# final.net
KiCad netlist of a schematic drawn in EAGLE
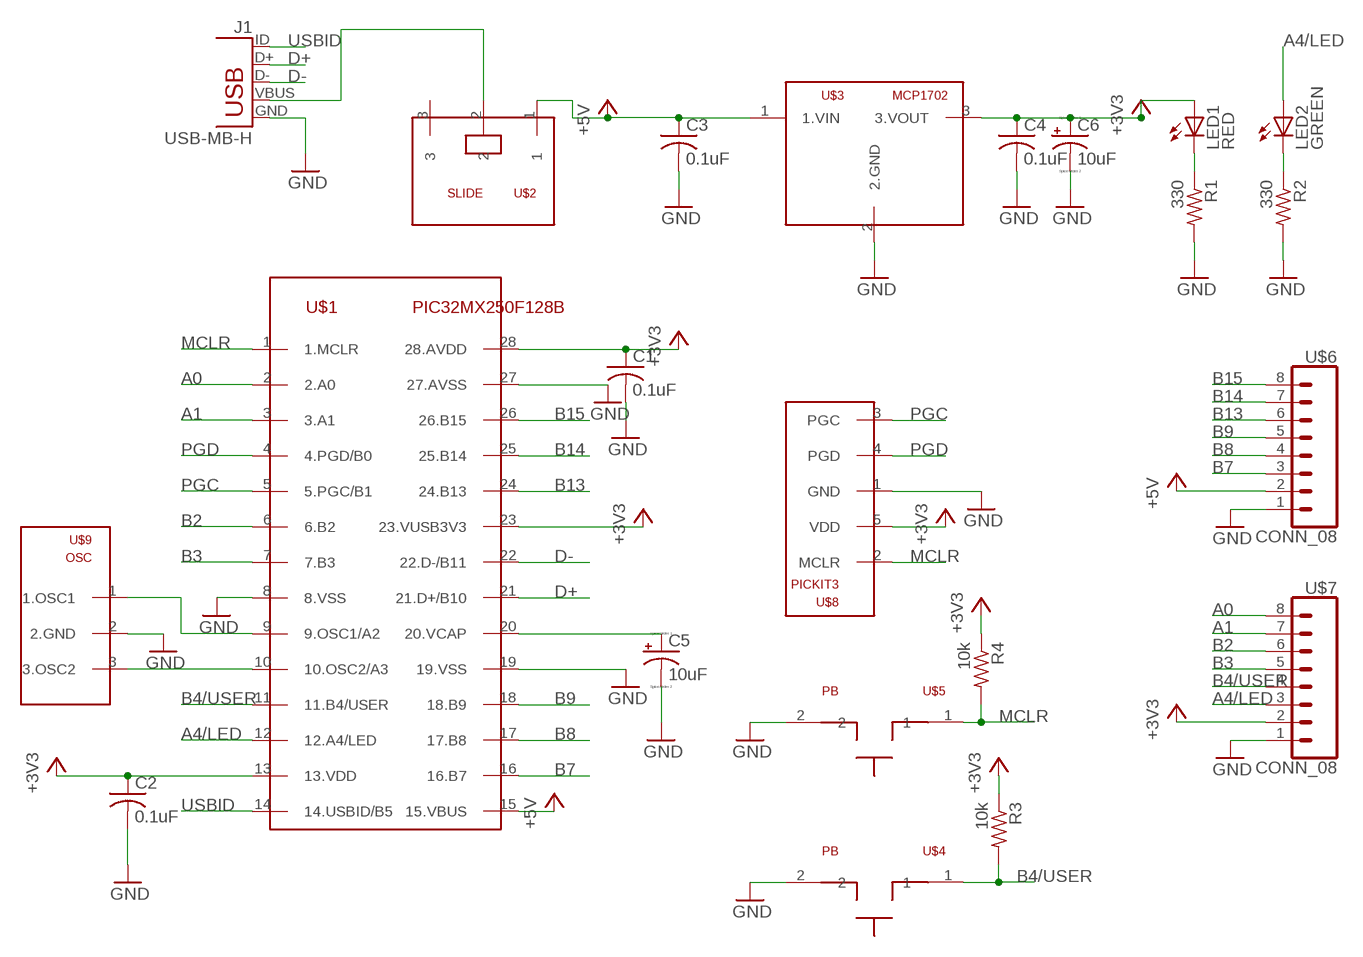
[diagram p0: schematic, sheet 1]

(export (version "E")
  (design (tool "Eeschema 10.0.6"))
  (components
    (comp (ref "C1")
      (value "0.1uF")
      (footprint "eagle-import:C025-025X050")
      (libsource (lib "eagle-import") (part "C-US025-025X050"))
    )
    (comp (ref "C2")
      (value "0.1uF")
      (footprint "eagle-import:C025-025X050")
      (libsource (lib "eagle-import") (part "C-US025-025X050"))
    )
    (comp (ref "C3")
      (value "0.1uF")
      (footprint "eagle-import:C025-025X050")
      (libsource (lib "eagle-import") (part "C-US025-025X050"))
    )
    (comp (ref "C4")
      (value "0.1uF")
      (footprint "eagle-import:C025-025X050")
      (libsource (lib "eagle-import") (part "C-US025-025X050"))
    )
    (comp (ref "C5")
      (value "10uF")
      (footprint "eagle-import:B45181B")
      (libsource (lib "eagle-import") (part "CPOL-USB45181B"))
    )
    (comp (ref "C6")
      (value "10uF")
      (footprint "eagle-import:B45181B")
      (libsource (lib "eagle-import") (part "CPOL-USB45181B"))
    )
    (comp (ref "J1")
      (value "USB-MB-H")
      (footprint "eagle-import:USB-MB-H")
      (libsource (lib "eagle-import") (part "USB-MB-H"))
    )
    (comp (ref "LED1")
      (value "RED")
      (footprint "eagle-import:LED3MM")
      (libsource (lib "eagle-import") (part "LED3MM"))
    )
    (comp (ref "LED2")
      (value "GREEN")
      (footprint "eagle-import:LED3MM")
      (libsource (lib "eagle-import") (part "LED3MM"))
    )
    (comp (ref "R1")
      (value "330")
      (footprint "eagle-import:0207_7")
      (libsource (lib "eagle-import") (part "R-US_0207/7"))
    )
    (comp (ref "R2")
      (value "330")
      (footprint "eagle-import:0207_7")
      (libsource (lib "eagle-import") (part "R-US_0207/7"))
    )
    (comp (ref "R3")
      (value "10k")
      (footprint "eagle-import:0207_7")
      (libsource (lib "eagle-import") (part "R-US_0207/7"))
    )
    (comp (ref "R4")
      (value "10k")
      (footprint "eagle-import:0207_7")
      (libsource (lib "eagle-import") (part "R-US_0207/7"))
    )
    (comp (ref "U$1")
      (value "PIC32MX250F128B")
      (footprint "eagle-import:DIL28-3")
      (libsource (lib "eagle-import") (part "PIC32MX250F128B"))
    )
    (comp (ref "U$2")
      (value "SLIDE")
      (footprint "eagle-import:SLIDE")
      (libsource (lib "eagle-import") (part "SLIDE"))
    )
    (comp (ref "U$3")
      (value "MCP1702")
      (footprint "eagle-import:TO92")
      (libsource (lib "eagle-import") (part "MCP1702"))
    )
    (comp (ref "U$4") (value "PB") (footprint "eagle-import:PB") (libsource (lib "eagle-import") (part "PB")))
    (comp (ref "U$5") (value "PB") (footprint "eagle-import:PB") (libsource (lib "eagle-import") (part "PB")))
    (comp (ref "U$6")
      (value "CONN_08")
      (footprint "eagle-import:1X08")
      (libsource (lib "eagle-import") (part "CONN_08"))
    )
    (comp (ref "U$7")
      (value "CONN_08")
      (footprint "eagle-import:1X08")
      (libsource (lib "eagle-import") (part "CONN_08"))
    )
    (comp (ref "U$8")
      (value "PICKIT3")
      (footprint "eagle-import:1X05")
      (libsource (lib "eagle-import") (part "PICKIT3"))
    )
    (comp (ref "U$9")
      (value "OSC")
      (footprint "eagle-import:OSC")
      (libsource (lib "eagle-import") (part "OSC"))
    )
  )
  (nets
    (net (code "1") (name "+3V3") (class "Default")
      (node (ref "C1") (pin "1") (pinfunction "1_1") (pintype "passive"))
      (node (ref "C2") (pin "1") (pinfunction "1_1") (pintype "passive"))
      (node (ref "C4") (pin "1") (pinfunction "1_1") (pintype "passive"))
      (node (ref "C6") (pin "+") (pinfunction "+_+") (pintype "passive"))
      (node (ref "LED1") (pin "A") (pinfunction "A_A") (pintype "passive"))
      (node (ref "R3") (pin "1") (pinfunction "1_1") (pintype "passive"))
      (node (ref "R4") (pin "1") (pinfunction "1_1") (pintype "passive"))
      (node (ref "U$1") (pin "13") (pinfunction "13.VDD_13") (pintype "bidirectional"))
      (node (ref "U$1") (pin "23") (pinfunction "23.VUSB3V3_23") (pintype "bidirectional"))
      (node (ref "U$1") (pin "28") (pinfunction "28.AVDD_28") (pintype "bidirectional"))
      (node (ref "U$3") (pin "3") (pinfunction "3.VOUT_3") (pintype "bidirectional"))
      (node (ref "U$7") (pin "2") (pinfunction "2_2") (pintype "passive"))
      (node (ref "U$8") (pin "5") (pinfunction "VDD_5") (pintype "bidirectional"))
    )
    (net (code "2") (name "+5V") (class "Default")
      (node (ref "C3") (pin "1") (pinfunction "1_1") (pintype "passive"))
      (node (ref "U$1") (pin "15") (pinfunction "15.VBUS_15") (pintype "bidirectional"))
      (node (ref "U$2") (pin "1") (pinfunction "1_1") (pintype "bidirectional"))
      (node (ref "U$3") (pin "1") (pinfunction "1.VIN_1") (pintype "bidirectional"))
      (node (ref "U$6") (pin "2") (pinfunction "2_2") (pintype "passive"))
    )
    (net (code "3") (name "/A0") (class "Default")
      (node (ref "U$1") (pin "2") (pinfunction "2.A0_2") (pintype "bidirectional"))
      (node (ref "U$7") (pin "8") (pinfunction "8_8") (pintype "passive"))
    )
    (net (code "4") (name "/A1") (class "Default")
      (node (ref "U$1") (pin "3") (pinfunction "3.A1_3") (pintype "bidirectional"))
      (node (ref "U$7") (pin "7") (pinfunction "7_7") (pintype "passive"))
    )
    (net (code "5") (name "/A4{slash}LED") (class "Default")
      (node (ref "LED2") (pin "A") (pinfunction "A_A") (pintype "passive"))
      (node (ref "U$1") (pin "12") (pinfunction "12.A4/LED_12") (pintype "bidirectional"))
      (node (ref "U$7") (pin "3") (pinfunction "3_3") (pintype "passive"))
    )
    (net (code "6") (name "/B2") (class "Default")
      (node (ref "U$1") (pin "6") (pinfunction "6.B2_6") (pintype "bidirectional"))
      (node (ref "U$7") (pin "6") (pinfunction "6_6") (pintype "passive"))
    )
    (net (code "7") (name "/B3") (class "Default")
      (node (ref "U$1") (pin "7") (pinfunction "7.B3_7") (pintype "bidirectional"))
      (node (ref "U$7") (pin "5") (pinfunction "5_5") (pintype "passive"))
    )
    (net (code "8") (name "/B4{slash}USER") (class "Default")
      (node (ref "R3") (pin "2") (pinfunction "2_2") (pintype "passive"))
      (node (ref "U$1") (pin "11") (pinfunction "11.B4/USER_11") (pintype "bidirectional"))
      (node (ref "U$4") (pin "1") (pinfunction "1_1") (pintype "bidirectional"))
      (node (ref "U$7") (pin "4") (pinfunction "4_4") (pintype "passive"))
    )
    (net (code "9") (name "/B7") (class "Default")
      (node (ref "U$1") (pin "16") (pinfunction "16.B7_16") (pintype "bidirectional"))
      (node (ref "U$6") (pin "3") (pinfunction "3_3") (pintype "passive"))
    )
    (net (code "10") (name "/B8") (class "Default")
      (node (ref "U$1") (pin "17") (pinfunction "17.B8_17") (pintype "bidirectional"))
      (node (ref "U$6") (pin "4") (pinfunction "4_4") (pintype "passive"))
    )
    (net (code "11") (name "/B9") (class "Default")
      (node (ref "U$1") (pin "18") (pinfunction "18.B9_18") (pintype "bidirectional"))
      (node (ref "U$6") (pin "5") (pinfunction "5_5") (pintype "passive"))
    )
    (net (code "12") (name "/B13") (class "Default")
      (node (ref "U$1") (pin "24") (pinfunction "24.B13_24") (pintype "bidirectional"))
      (node (ref "U$6") (pin "6") (pinfunction "6_6") (pintype "passive"))
    )
    (net (code "13") (name "/B14") (class "Default")
      (node (ref "U$1") (pin "25") (pinfunction "25.B14_25") (pintype "bidirectional"))
      (node (ref "U$6") (pin "7") (pinfunction "7_7") (pintype "passive"))
    )
    (net (code "14") (name "/B15") (class "Default")
      (node (ref "U$1") (pin "26") (pinfunction "26.B15_26") (pintype "bidirectional"))
      (node (ref "U$6") (pin "8") (pinfunction "8_8") (pintype "passive"))
    )
    (net (code "15") (name "/D+") (class "Default")
      (node (ref "J1") (pin "D+") (pinfunction "D+_D+") (pintype "bidirectional"))
      (node (ref "U$1") (pin "21") (pinfunction "21.D+/B10_21") (pintype "bidirectional"))
    )
    (net (code "16") (name "/D-") (class "Default")
      (node (ref "J1") (pin "D-") (pinfunction "D-_D-") (pintype "bidirectional"))
      (node (ref "U$1") (pin "22") (pinfunction "22.D-/B11_22") (pintype "bidirectional"))
    )
    (net (code "17") (name "/MCLR") (class "Default")
      (node (ref "R4") (pin "2") (pinfunction "2_2") (pintype "passive"))
      (node (ref "U$1") (pin "1") (pinfunction "1.MCLR_1") (pintype "bidirectional"))
      (node (ref "U$5") (pin "1") (pinfunction "1_1") (pintype "bidirectional"))
      (node (ref "U$8") (pin "2") (pinfunction "MCLR_2") (pintype "bidirectional"))
    )
    (net (code "18") (name "/PGC") (class "Default")
      (node (ref "U$1") (pin "5") (pinfunction "5.PGC/B1_5") (pintype "bidirectional"))
      (node (ref "U$8") (pin "3") (pinfunction "PGC_3") (pintype "bidirectional"))
    )
    (net (code "19") (name "/PGD") (class "Default")
      (node (ref "U$1") (pin "4") (pinfunction "4.PGD/B0_4") (pintype "bidirectional"))
      (node (ref "U$8") (pin "4") (pinfunction "PGD_4") (pintype "bidirectional"))
    )
    (net (code "20") (name "/USBID") (class "Default")
      (node (ref "J1") (pin "ID") (pinfunction "ID_ID") (pintype "bidirectional"))
      (node (ref "U$1") (pin "14") (pinfunction "14.USBID/B5_14") (pintype "bidirectional"))
    )
    (net (code "21") (name "GND") (class "Default")
      (node (ref "C1") (pin "2") (pinfunction "2_2") (pintype "passive"))
      (node (ref "C2") (pin "2") (pinfunction "2_2") (pintype "passive"))
      (node (ref "C3") (pin "2") (pinfunction "2_2") (pintype "passive"))
      (node (ref "C4") (pin "2") (pinfunction "2_2") (pintype "passive"))
      (node (ref "C5") (pin "-") (pinfunction "-_-") (pintype "passive"))
      (node (ref "C6") (pin "-") (pinfunction "-_-") (pintype "passive"))
      (node (ref "J1") (pin "GND") (pinfunction "GND_GND") (pintype "bidirectional"))
      (node (ref "R1") (pin "2") (pinfunction "2_2") (pintype "passive"))
      (node (ref "R2") (pin "2") (pinfunction "2_2") (pintype "passive"))
      (node (ref "U$1") (pin "19") (pinfunction "19.VSS_19") (pintype "bidirectional"))
      (node (ref "U$1") (pin "27") (pinfunction "27.AVSS_27") (pintype "bidirectional"))
      (node (ref "U$1") (pin "8") (pinfunction "8.VSS_8") (pintype "bidirectional"))
      (node (ref "U$3") (pin "2") (pinfunction "2.GND_2") (pintype "bidirectional"))
      (node (ref "U$4") (pin "2") (pinfunction "2_2") (pintype "bidirectional"))
      (node (ref "U$5") (pin "2") (pinfunction "2_2") (pintype "bidirectional"))
      (node (ref "U$6") (pin "1") (pinfunction "1_1") (pintype "passive"))
      (node (ref "U$7") (pin "1") (pinfunction "1_1") (pintype "passive"))
      (node (ref "U$8") (pin "1") (pinfunction "GND_1") (pintype "bidirectional"))
      (node (ref "U$9") (pin "2") (pinfunction "2.GND_2") (pintype "bidirectional"))
    )
    (net (code "22") (name "Net-(J1-PadVBUS)") (class "Default")
      (node (ref "J1") (pin "VBUS") (pinfunction "VBUS_VBUS") (pintype "bidirectional"))
      (node (ref "U$2") (pin "2") (pinfunction "2_2") (pintype "bidirectional"))
    )
    (net (code "23") (name "Net-(LED1-C)") (class "Default")
      (node (ref "LED1") (pin "K") (pinfunction "C_K") (pintype "passive"))
      (node (ref "R1") (pin "1") (pinfunction "1_1") (pintype "passive"))
    )
    (net (code "24") (name "Net-(LED2-C)") (class "Default")
      (node (ref "LED2") (pin "K") (pinfunction "C_K") (pintype "passive"))
      (node (ref "R2") (pin "1") (pinfunction "1_1") (pintype "passive"))
    )
    (net (code "25") (name "Net-(U$1-9.OSC1{slash}A2)") (class "Default")
      (node (ref "U$1") (pin "9") (pinfunction "9.OSC1/A2_9") (pintype "bidirectional"))
      (node (ref "U$9") (pin "1") (pinfunction "1.OSC1_1") (pintype "bidirectional"))
    )
    (net (code "26") (name "Net-(U$1-10.OSC2{slash}A3)") (class "Default")
      (node (ref "U$1") (pin "10") (pinfunction "10.OSC2/A3_10") (pintype "bidirectional"))
      (node (ref "U$9") (pin "3") (pinfunction "3.OSC2_3") (pintype "bidirectional"))
    )
    (net (code "27") (name "Net-(U$1-20.VCAP)") (class "Default")
      (node (ref "C5") (pin "+") (pinfunction "+_+") (pintype "passive"))
      (node (ref "U$1") (pin "20") (pinfunction "20.VCAP_20") (pintype "bidirectional"))
    )
    (net (code "28") (name "unconnected-(U$2-Pad3)") (class "Default")
      (node (ref "U$2") (pin "3") (pinfunction "3_3") (pintype "bidirectional"))
    )
  )
)
